# ardBeeQueenWMountHolesWMountedRelays105x.net
KiCad netlist of a schematic drawn in EAGLE
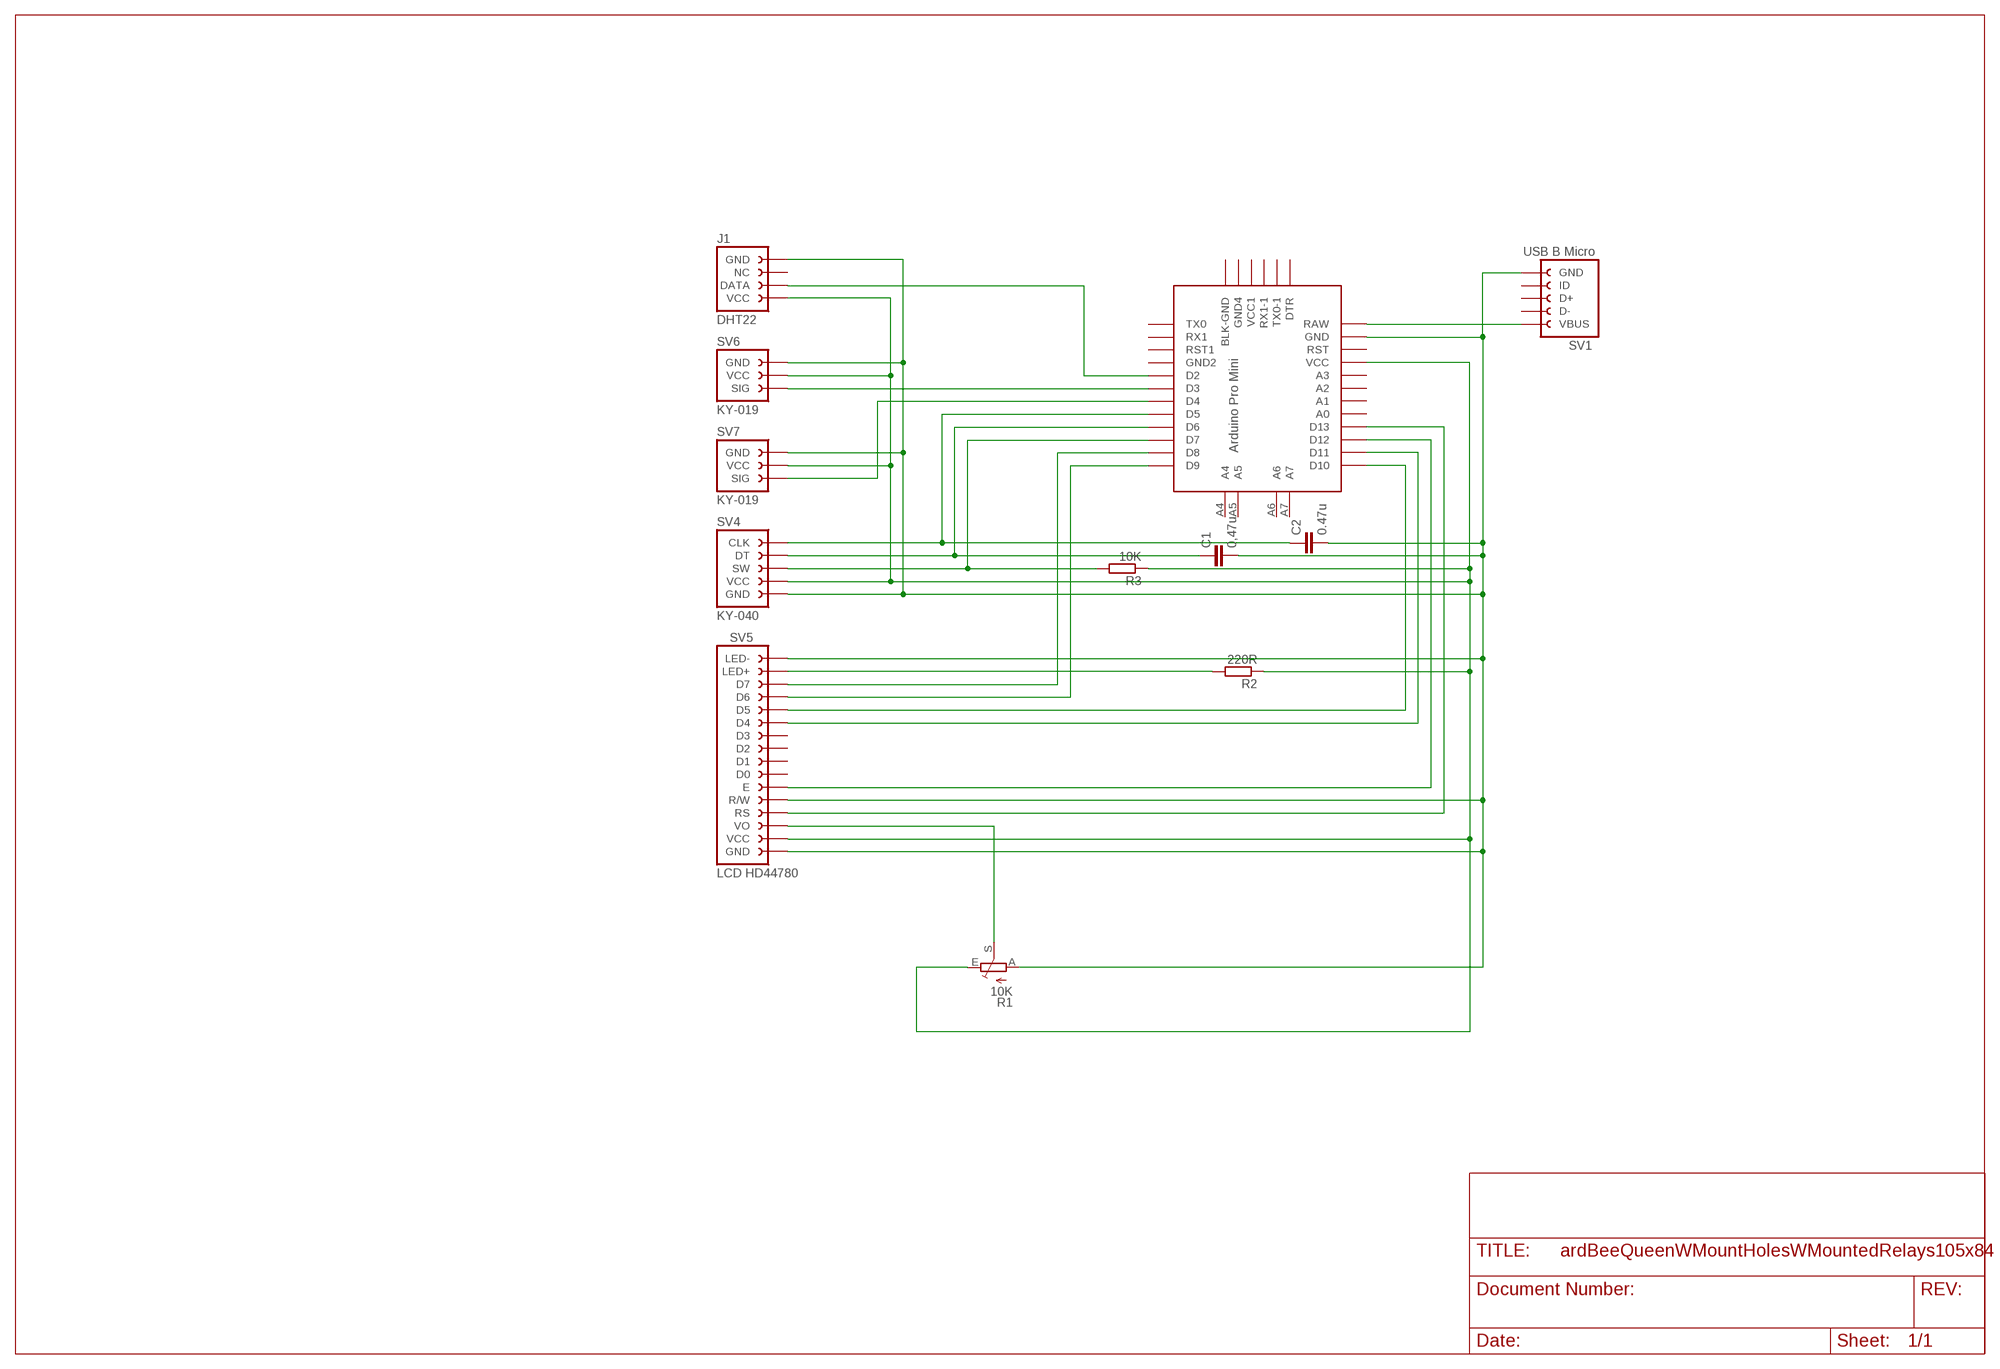
[diagram p0: schematic, sheet 1]

(export (version "E")
  (design (tool "Eeschema 10.0.6"))
  (components
    (comp (ref "C1")
      (value "0,47u")
      (footprint "eagle-import:C050-024X044")
      (libsource (lib "eagle-import") (part "C-EU050-024X044"))
    )
    (comp (ref "C2")
      (value "0.47u")
      (footprint "eagle-import:C050-024X044")
      (libsource (lib "eagle-import") (part "C-EU050-024X044"))
    )
    (comp (ref "J1")
      (value "DHT22_4-PIN_FEMALE_HEADERPTH")
      (footprint "eagle-import:DHT22_4-PIN_FEMALE_HEADER")
      (libsource (lib "eagle-import") (part "DHT22_4-PIN_FEMALE_HEADERPTH"))
    )
    (comp (ref "R1")
      (value "10K")
      (footprint "eagle-import:B25P")
      (libsource (lib "eagle-import") (part "TRIM_EU-B25P"))
    )
    (comp (ref "R2")
      (value "220R")
      (footprint "eagle-import:0207_10")
      (libsource (lib "eagle-import") (part "R-EU_0207/10"))
    )
    (comp (ref "R3")
      (value "10K")
      (footprint "eagle-import:0207_10")
      (libsource (lib "eagle-import") (part "R-EU_0207/10"))
    )
    (comp (ref "SV1")
      (value "MICROUSB_B_BREAKOUT_5-PIN_FEMALE_HEADERWITH_MOUNT_HOLES")
      (footprint "eagle-import:MICROUSB_B_BREAKOUT_5-PIN_FEMALE_HEADER_W_MOUNT_HOLES")
      (libsource (lib "eagle-import") (part "MICROUSB_B_BREAKOUT_5-PIN_FEMALE_HEADERWITH_MOUNT_HOLES"))
    )
    (comp (ref "SV4")
      (value "KY-040_5-PIN_FEMALE_HEADER")
      (footprint "eagle-import:KY-040_5-PIN_FEMALE_HEADER")
      (libsource (lib "eagle-import") (part "KY-040_5-PIN_FEMALE_HEADER"))
    )
    (comp (ref "SV5")
      (value "LCD-HD44780-16-PIN_FEMALE_HEADER")
      (footprint "eagle-import:LCD-HD44780-16-PIN_FEMALE_HEADER")
      (libsource (lib "eagle-import") (part "LCD-HD44780-16-PIN_FEMALE_HEADER"))
    )
    (comp (ref "SV6")
      (value "KY-019_3-PIN_FEMALE_HEADERANGLED_W_MOUNT_HOLES")
      (footprint "eagle-import:KY-019_3-PIN_FEMALE_HEADER_ANGLED_W_MOUNT_HOLES")
      (libsource (lib "eagle-import") (part "KY-019_3-PIN_FEMALE_HEADERANGLED_W_MOUNT_HOLES"))
    )
    (comp (ref "SV7")
      (value "KY-019_3-PIN_FEMALE_HEADERANGLED_W_MOUNT_HOLES")
      (footprint "eagle-import:KY-019_3-PIN_FEMALE_HEADER_ANGLED_W_MOUNT_HOLES")
      (libsource (lib "eagle-import") (part "KY-019_3-PIN_FEMALE_HEADERANGLED_W_MOUNT_HOLES"))
    )
    (comp (ref "U$1")
      (value "ARDUINO_PRO_MINI-2")
      (footprint "eagle-import:ARDUINO_PRO_MINI-2")
      (libsource (lib "eagle-import") (part "ARDUINO_PRO_MINI-2"))
    )
  )
  (nets
    (net (code "1") (name "Net-(C1-Pad1)") (class "Default")
      (node (ref "C1") (pin "1") (pinfunction "1_1") (pintype "passive"))
      (node (ref "SV4") (pin "DT") (pinfunction "DT_DT") (pintype "passive"))
      (node (ref "U$1") (pin "D6") (pinfunction "D6_D6") (pintype "bidirectional"))
    )
    (net (code "2") (name "Net-(C1-Pad2)") (class "Default")
      (node (ref "C1") (pin "2") (pinfunction "2_2") (pintype "passive"))
      (node (ref "C2") (pin "2") (pinfunction "2_2") (pintype "passive"))
      (node (ref "J1") (pin "GND") (pinfunction "GND_GND") (pintype "passive"))
      (node (ref "R1") (pin "A") (pinfunction "A_A") (pintype "passive"))
      (node (ref "SV1") (pin "GND") (pinfunction "GND_GND") (pintype "passive"))
      (node (ref "SV4") (pin "GND") (pinfunction "GND_GND") (pintype "passive"))
      (node (ref "SV5") (pin "GND") (pinfunction "GND_GND") (pintype "passive"))
      (node (ref "SV5") (pin "LED-") (pinfunction "LED-_LED-") (pintype "passive"))
      (node (ref "SV5") (pin "R/W") (pinfunction "R/W_R/W") (pintype "passive"))
      (node (ref "SV6") (pin "GND") (pinfunction "GND_GND") (pintype "passive"))
      (node (ref "SV7") (pin "GND") (pinfunction "GND_GND") (pintype "passive"))
      (node (ref "U$1") (pin "GND") (pinfunction "GND_GND") (pintype "bidirectional"))
    )
    (net (code "3") (name "Net-(C2-Pad1)") (class "Default")
      (node (ref "C2") (pin "1") (pinfunction "1_1") (pintype "passive"))
      (node (ref "SV4") (pin "CLK") (pinfunction "CLK_CLK") (pintype "passive"))
      (node (ref "U$1") (pin "D5") (pinfunction "D5_D5") (pintype "bidirectional"))
    )
    (net (code "4") (name "Net-(J1-PadDATA)") (class "Default")
      (node (ref "J1") (pin "DATA") (pinfunction "DATA_DATA") (pintype "passive"))
      (node (ref "U$1") (pin "D2") (pinfunction "D2_D2") (pintype "bidirectional"))
    )
    (net (code "5") (name "Net-(J1-PadVCC)") (class "Default")
      (node (ref "J1") (pin "VCC") (pinfunction "VCC_VCC") (pintype "passive"))
      (node (ref "R1") (pin "E") (pinfunction "E_E") (pintype "passive"))
      (node (ref "R2") (pin "1") (pinfunction "1_1") (pintype "passive"))
      (node (ref "R3") (pin "1") (pinfunction "1_1") (pintype "passive"))
      (node (ref "SV4") (pin "VCC") (pinfunction "VCC_VCC") (pintype "passive"))
      (node (ref "SV5") (pin "VCC") (pinfunction "VCC_VCC") (pintype "passive"))
      (node (ref "SV6") (pin "VCC") (pinfunction "VCC_VCC") (pintype "passive"))
      (node (ref "SV7") (pin "VCC") (pinfunction "VCC_VCC") (pintype "passive"))
      (node (ref "U$1") (pin "VCC") (pinfunction "VCC_VCC") (pintype "bidirectional"))
    )
    (net (code "6") (name "Net-(R1-PadS)") (class "Default")
      (node (ref "R1") (pin "S") (pinfunction "S_S") (pintype "passive"))
      (node (ref "SV5") (pin "VO") (pinfunction "VO_VO") (pintype "passive"))
    )
    (net (code "7") (name "Net-(R2-Pad2)") (class "Default")
      (node (ref "R2") (pin "2") (pinfunction "2_2") (pintype "passive"))
      (node (ref "SV5") (pin "LED+") (pinfunction "LED+_LED+") (pintype "passive"))
    )
    (net (code "8") (name "Net-(R3-Pad2)") (class "Default")
      (node (ref "R3") (pin "2") (pinfunction "2_2") (pintype "passive"))
      (node (ref "SV4") (pin "SW") (pinfunction "SW_SW") (pintype "passive"))
      (node (ref "U$1") (pin "D7") (pinfunction "D7_D7") (pintype "bidirectional"))
    )
    (net (code "9") (name "Net-(SV1-PadVBUS)") (class "Default")
      (node (ref "SV1") (pin "VBUS") (pinfunction "VBUS_VBUS") (pintype "passive"))
      (node (ref "U$1") (pin "RAW") (pinfunction "RAW_RAW") (pintype "bidirectional"))
    )
    (net (code "10") (name "Net-(SV5-PadD4)") (class "Default")
      (node (ref "SV5") (pin "D4") (pinfunction "D4_D4") (pintype "passive"))
      (node (ref "U$1") (pin "D11") (pinfunction "D11_D11") (pintype "bidirectional"))
    )
    (net (code "11") (name "Net-(SV5-PadD5)") (class "Default")
      (node (ref "SV5") (pin "D5") (pinfunction "D5_D5") (pintype "passive"))
      (node (ref "U$1") (pin "D10") (pinfunction "D10_D10") (pintype "bidirectional"))
    )
    (net (code "12") (name "Net-(SV5-PadD6)") (class "Default")
      (node (ref "SV5") (pin "D6") (pinfunction "D6_D6") (pintype "passive"))
      (node (ref "U$1") (pin "D9") (pinfunction "D9_D9") (pintype "bidirectional"))
    )
    (net (code "13") (name "Net-(SV5-PadD7)") (class "Default")
      (node (ref "SV5") (pin "D7") (pinfunction "D7_D7") (pintype "passive"))
      (node (ref "U$1") (pin "D8") (pinfunction "D8_D8") (pintype "bidirectional"))
    )
    (net (code "14") (name "Net-(SV5-PadE)") (class "Default")
      (node (ref "SV5") (pin "E") (pinfunction "E_E") (pintype "passive"))
      (node (ref "U$1") (pin "D12") (pinfunction "D12_D12") (pintype "bidirectional"))
    )
    (net (code "15") (name "Net-(SV5-PadRS)") (class "Default")
      (node (ref "SV5") (pin "RS") (pinfunction "RS_RS") (pintype "passive"))
      (node (ref "U$1") (pin "D13") (pinfunction "D13_D13") (pintype "bidirectional"))
    )
    (net (code "16") (name "Net-(SV6-PadSIG)") (class "Default")
      (node (ref "SV6") (pin "SIG") (pinfunction "SIG_SIG") (pintype "passive"))
      (node (ref "U$1") (pin "D3") (pinfunction "D3_D3") (pintype "bidirectional"))
    )
    (net (code "17") (name "Net-(SV7-PadSIG)") (class "Default")
      (node (ref "SV7") (pin "SIG") (pinfunction "SIG_SIG") (pintype "passive"))
      (node (ref "U$1") (pin "D4") (pinfunction "D4_D4") (pintype "bidirectional"))
    )
    (net (code "18") (name "unconnected-(J1-PadNC)") (class "Default")
      (node (ref "J1") (pin "NC") (pinfunction "NC_NC") (pintype "passive"))
    )
    (net (code "19") (name "unconnected-(SV1-PadD+)") (class "Default")
      (node (ref "SV1") (pin "D+") (pinfunction "D+_D+") (pintype "passive"))
    )
    (net (code "20") (name "unconnected-(SV1-PadD-)") (class "Default")
      (node (ref "SV1") (pin "D-") (pinfunction "D-_D-") (pintype "passive"))
    )
    (net (code "21") (name "unconnected-(SV1-PadID)") (class "Default")
      (node (ref "SV1") (pin "ID") (pinfunction "ID_ID") (pintype "passive"))
    )
    (net (code "22") (name "unconnected-(SV5-PadD0)") (class "Default")
      (node (ref "SV5") (pin "D0") (pinfunction "D0_D0") (pintype "passive"))
    )
    (net (code "23") (name "unconnected-(SV5-PadD1)") (class "Default")
      (node (ref "SV5") (pin "D1") (pinfunction "D1_D1") (pintype "passive"))
    )
    (net (code "24") (name "unconnected-(SV5-PadD2)") (class "Default")
      (node (ref "SV5") (pin "D2") (pinfunction "D2_D2") (pintype "passive"))
    )
    (net (code "25") (name "unconnected-(SV5-PadD3)") (class "Default")
      (node (ref "SV5") (pin "D3") (pinfunction "D3_D3") (pintype "passive"))
    )
    (net (code "26") (name "unconnected-(U$1-GND2-PadGND1)") (class "Default")
      (node (ref "U$1") (pin "GND1") (pinfunction "GND2_GND1") (pintype "bidirectional"))
    )
    (net (code "27") (name "unconnected-(U$1-GND4-PadGND3)") (class "Default")
      (node (ref "U$1") (pin "GND3") (pinfunction "GND4_GND3") (pintype "bidirectional"))
    )
    (net (code "28") (name "unconnected-(U$1-PadA0)") (class "Default")
      (node (ref "U$1") (pin "A0") (pinfunction "A0_A0") (pintype "bidirectional"))
    )
    (net (code "29") (name "unconnected-(U$1-PadA1)") (class "Default")
      (node (ref "U$1") (pin "A1") (pinfunction "A1_A1") (pintype "bidirectional"))
    )
    (net (code "30") (name "unconnected-(U$1-PadA2)") (class "Default")
      (node (ref "U$1") (pin "A2") (pinfunction "A2_A2") (pintype "bidirectional"))
    )
    (net (code "31") (name "unconnected-(U$1-PadA3)") (class "Default")
      (node (ref "U$1") (pin "A3") (pinfunction "A3_A3") (pintype "bidirectional"))
    )
    (net (code "32") (name "unconnected-(U$1-PadA4)") (class "Default")
      (node (ref "U$1") (pin "A4") (pinfunction "A4_A4") (pintype "bidirectional"))
    )
    (net (code "33") (name "unconnected-(U$1-PadA5)") (class "Default")
      (node (ref "U$1") (pin "A5") (pinfunction "A5_A5") (pintype "bidirectional"))
    )
    (net (code "34") (name "unconnected-(U$1-PadA6)") (class "Default")
      (node (ref "U$1") (pin "A6") (pinfunction "A6_A6") (pintype "bidirectional"))
    )
    (net (code "35") (name "unconnected-(U$1-PadA7)") (class "Default")
      (node (ref "U$1") (pin "A7") (pinfunction "A7_A7") (pintype "bidirectional"))
    )
    (net (code "36") (name "unconnected-(U$1-PadBLK-GND)") (class "Default")
      (node (ref "U$1") (pin "BLK-GND") (pinfunction "BLK-GND_BLK-GND") (pintype "bidirectional"))
    )
    (net (code "37") (name "unconnected-(U$1-PadDTR)") (class "Default")
      (node (ref "U$1") (pin "DTR") (pinfunction "DTR_DTR") (pintype "bidirectional"))
    )
    (net (code "38") (name "unconnected-(U$1-PadRST)") (class "Default")
      (node (ref "U$1") (pin "RST") (pinfunction "RST_RST") (pintype "bidirectional"))
    )
    (net (code "39") (name "unconnected-(U$1-PadRST1)") (class "Default")
      (node (ref "U$1") (pin "RST1") (pinfunction "RST1_RST1") (pintype "bidirectional"))
    )
    (net (code "40") (name "unconnected-(U$1-PadRX1)") (class "Default")
      (node (ref "U$1") (pin "RX1") (pinfunction "RX1_RX1") (pintype "bidirectional"))
    )
    (net (code "41") (name "unconnected-(U$1-PadRX1-1)") (class "Default")
      (node (ref "U$1") (pin "RX1-1") (pinfunction "RX1-1_RX1-1") (pintype "bidirectional"))
    )
    (net (code "42") (name "unconnected-(U$1-PadTX0)") (class "Default")
      (node (ref "U$1") (pin "TX0") (pinfunction "TX0_TX0") (pintype "bidirectional"))
    )
    (net (code "43") (name "unconnected-(U$1-PadTX0-1)") (class "Default")
      (node (ref "U$1") (pin "TX0-1") (pinfunction "TX0-1_TX0-1") (pintype "bidirectional"))
    )
    (net (code "44") (name "unconnected-(U$1-PadVCC1)") (class "Default")
      (node (ref "U$1") (pin "VCC1") (pinfunction "VCC1_VCC1") (pintype "bidirectional"))
    )
  )
)
